# 1-Schematic_Spirulina_controler_board.net
KiCad netlist of a schematic drawn in EasyEDA
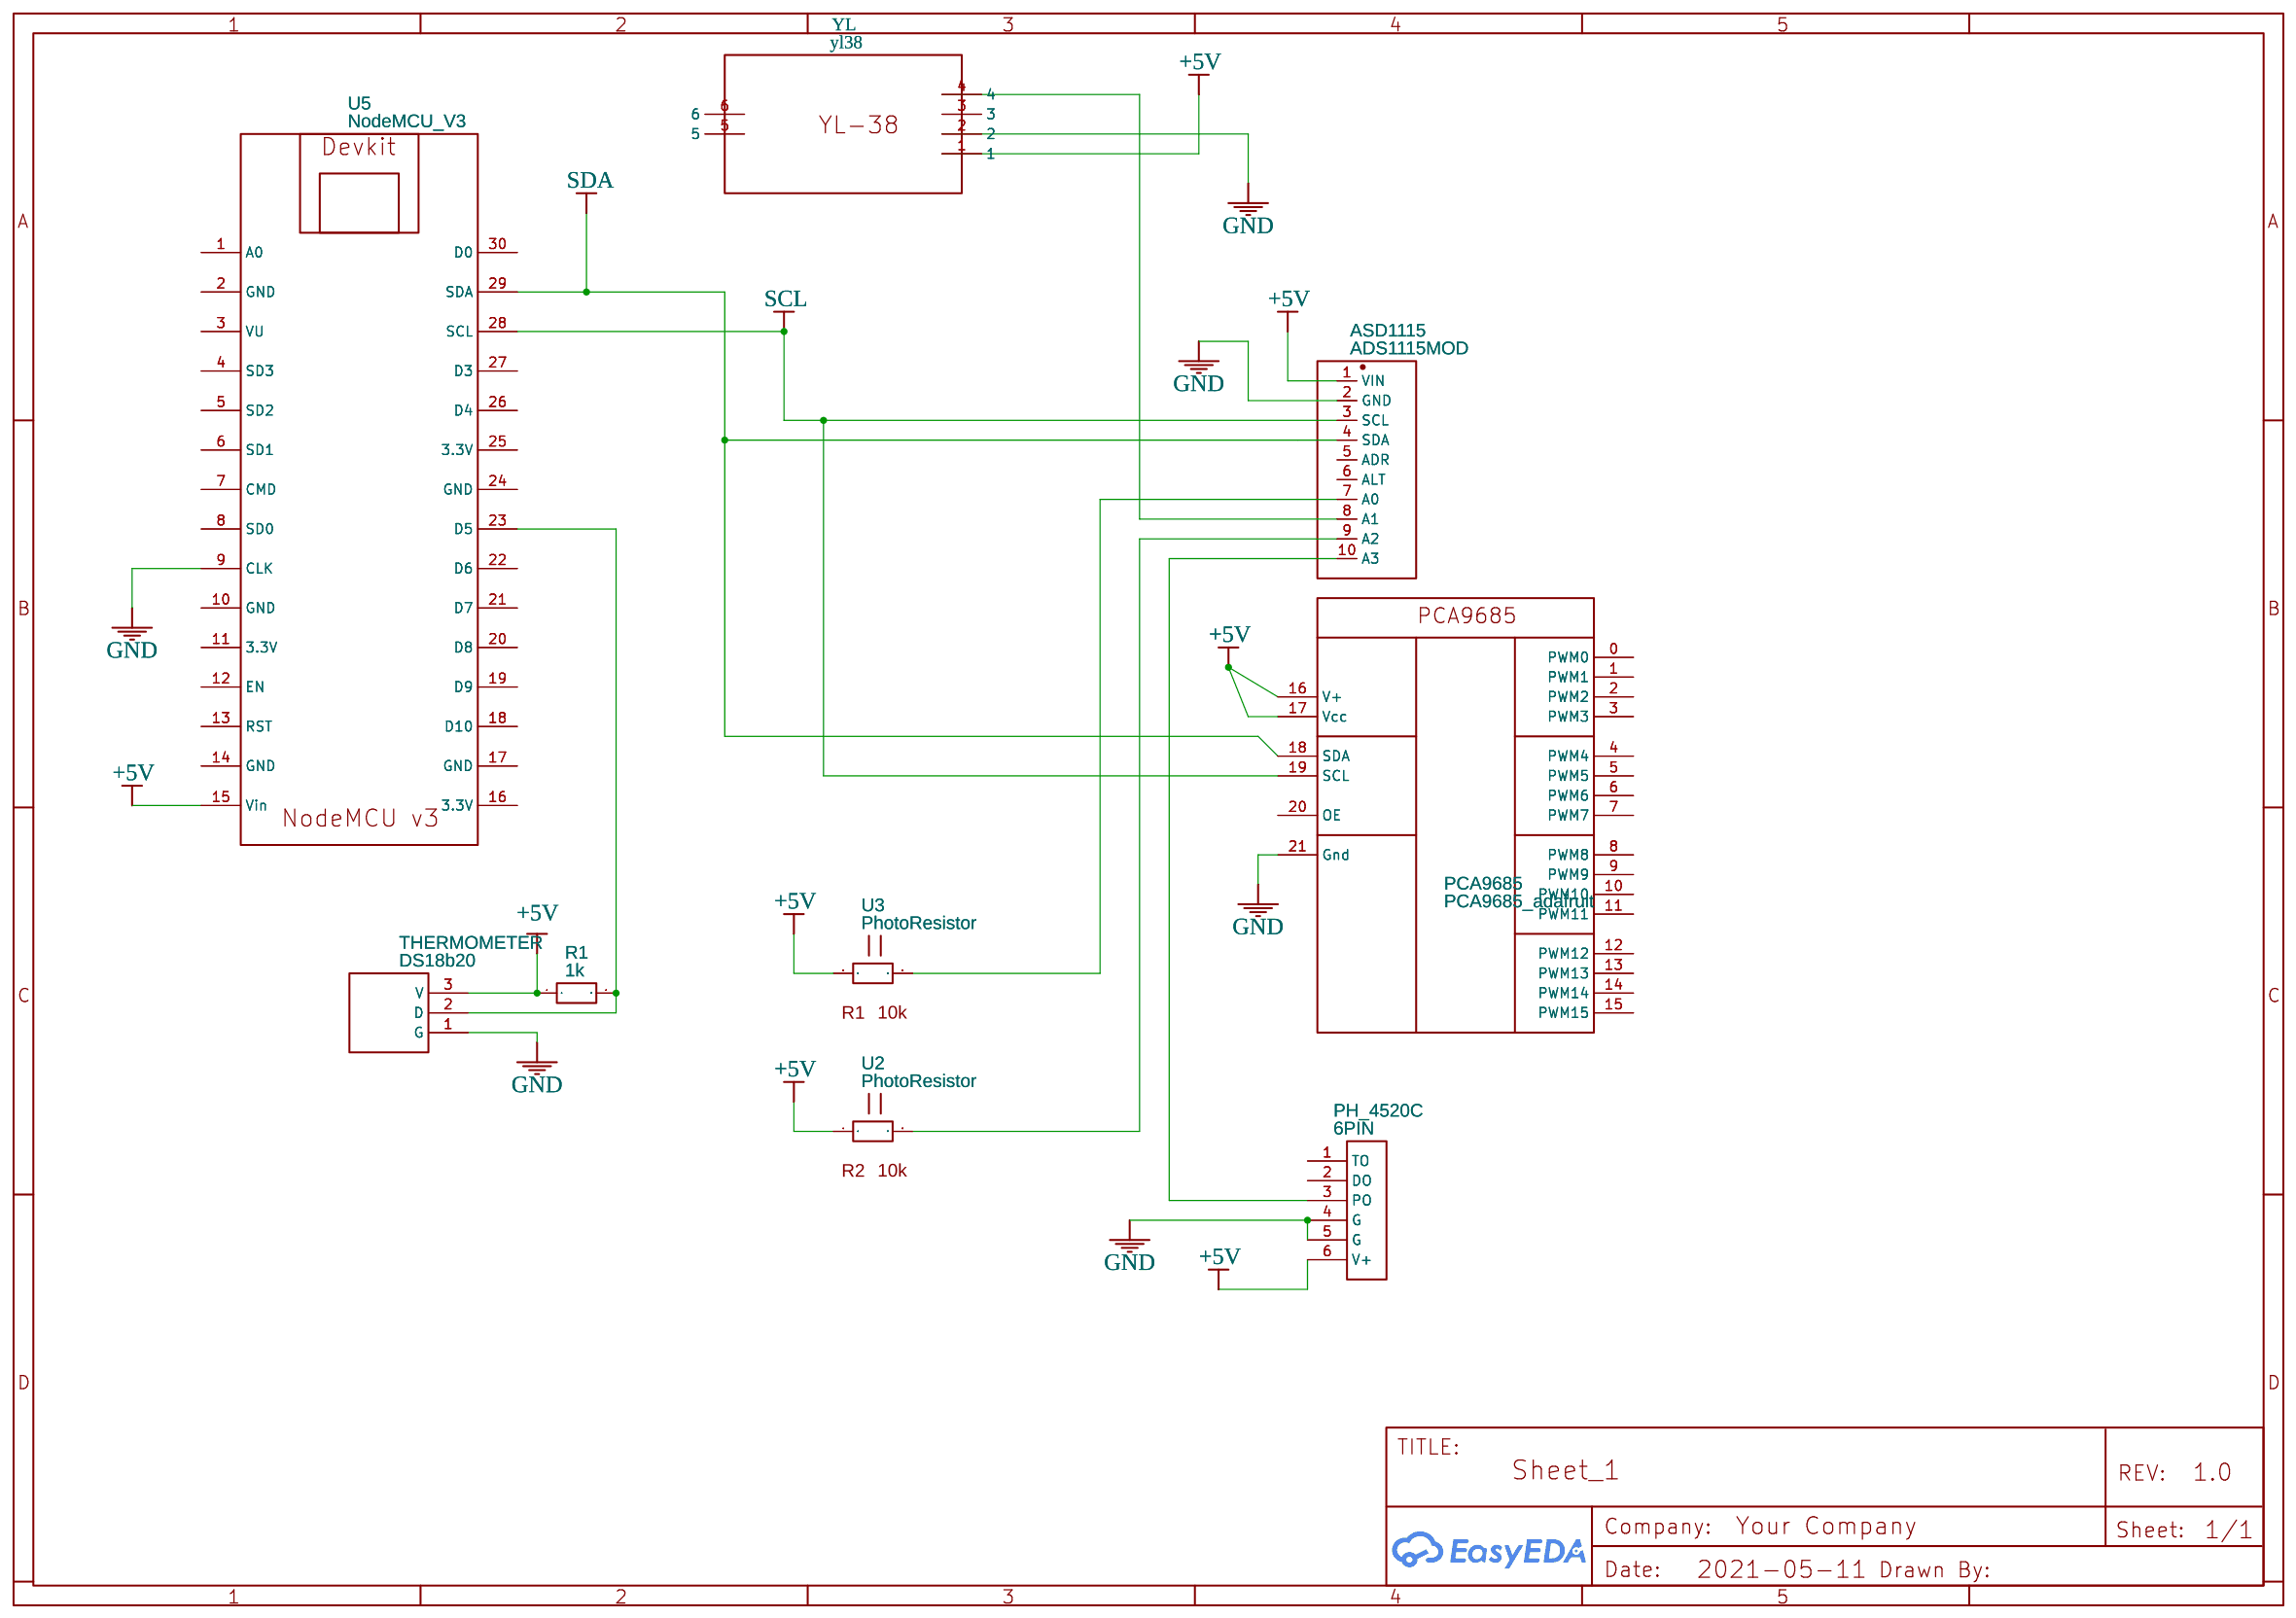
[diagram p0: schematic sheet]

(export (version "E")
  (design (tool "Eeschema 10.0.6"))
  (components
    (comp (ref "ASD1115") (value "ADS1115MOD") (libsource (lib "") (part "ADS1115MOD")))
    (comp (ref "PCA9685") (value "PCA9685_adafruit") (libsource (lib "") (part "PCA9685_adafruit")))
    (comp (ref "PH_4520C") (value "6PIN") (libsource (lib "") (part "6PIN")))
    (comp (ref "R1") (value "1k") (libsource (lib "") (part "R_0201_EU")))
    (comp (ref "THERMOMETER") (value "DS18b20") (libsource (lib "") (part "DS18b20")))
    (comp (ref "U2") (value "PhotoResistor") (libsource (lib "") (part "PhotoResistor_1")))
    (comp (ref "U3") (value "PhotoResistor") (libsource (lib "") (part "PhotoResistor")))
    (comp (ref "U5") (value "NodeMCU_V3") (libsource (lib "") (part "NodeMCU_V3")))
    (comp (ref "YL") (value "yl38") (libsource (lib "") (part "Unknown_420_-755")))
  )
  (nets
    (net (code "1") (name "+5V") (class "Default")
      (node (ref "ASD1115") (pin "1") (pinfunction "VIN_1") (pintype "unspecified"))
      (node (ref "PCA9685") (pin "16") (pinfunction "V+_16") (pintype "unspecified"))
      (node (ref "PCA9685") (pin "17") (pinfunction "Vcc_17") (pintype "unspecified"))
      (node (ref "PH_4520C") (pin "6") (pinfunction "V+_6") (pintype "unspecified"))
      (node (ref "R1") (pin "1") (pinfunction "1_1") (pintype "unspecified"))
      (node (ref "THERMOMETER") (pin "3") (pinfunction "V_3") (pintype "unspecified"))
      (node (ref "U2") (pin "1") (pinfunction "1_1") (pintype "unspecified"))
      (node (ref "U3") (pin "1") (pinfunction "1_1") (pintype "unspecified"))
      (node (ref "U5") (pin "15") (pinfunction "Vin_15") (pintype "unspecified"))
      (node (ref "YL") (pin "1") (pinfunction "1_1") (pintype "unspecified"))
    )
    (net (code "2") (name "GND") (class "Default")
      (node (ref "ASD1115") (pin "2") (pinfunction "GND_2") (pintype "unspecified"))
      (node (ref "PCA9685") (pin "21") (pinfunction "Gnd_21") (pintype "unspecified"))
      (node (ref "PH_4520C") (pin "4") (pinfunction "G_4") (pintype "unspecified"))
      (node (ref "PH_4520C") (pin "5") (pinfunction "G_5") (pintype "unspecified"))
      (node (ref "THERMOMETER") (pin "1") (pinfunction "G_1") (pintype "unspecified"))
      (node (ref "U5") (pin "9") (pinfunction "CLK_9") (pintype "unspecified"))
      (node (ref "YL") (pin "2") (pinfunction "2_2") (pintype "unspecified"))
    )
    (net (code "3") (name "Net-(ASD1115-A0)") (class "Default")
      (node (ref "ASD1115") (pin "7") (pinfunction "A0_7") (pintype "unspecified"))
      (node (ref "U3") (pin "2") (pinfunction "2_2") (pintype "unspecified"))
    )
    (net (code "4") (name "Net-(ASD1115-A1)") (class "Default")
      (node (ref "ASD1115") (pin "8") (pinfunction "A1_8") (pintype "unspecified"))
      (node (ref "YL") (pin "4") (pinfunction "4_4") (pintype "unspecified"))
    )
    (net (code "5") (name "Net-(ASD1115-A2)") (class "Default")
      (node (ref "ASD1115") (pin "9") (pinfunction "A2_9") (pintype "unspecified"))
      (node (ref "U2") (pin "2") (pinfunction "2_2") (pintype "unspecified"))
    )
    (net (code "6") (name "Net-(ASD1115-A3)") (class "Default")
      (node (ref "ASD1115") (pin "10") (pinfunction "A3_10") (pintype "unspecified"))
      (node (ref "PH_4520C") (pin "3") (pinfunction "PO_3") (pintype "unspecified"))
    )
    (net (code "7") (name "Net-(THERMOMETER-D)") (class "Default")
      (node (ref "R1") (pin "2") (pinfunction "2_2") (pintype "unspecified"))
      (node (ref "THERMOMETER") (pin "2") (pinfunction "D_2") (pintype "unspecified"))
      (node (ref "U5") (pin "23") (pinfunction "D5_23") (pintype "unspecified"))
    )
    (net (code "8") (name "SCL") (class "Default")
      (node (ref "ASD1115") (pin "3") (pinfunction "SCL_3") (pintype "unspecified"))
      (node (ref "PCA9685") (pin "19") (pinfunction "SCL_19") (pintype "unspecified"))
      (node (ref "U5") (pin "28") (pinfunction "SCL_28") (pintype "unspecified"))
    )
    (net (code "9") (name "SDA") (class "Default")
      (node (ref "ASD1115") (pin "4") (pinfunction "SDA_4") (pintype "unspecified"))
      (node (ref "PCA9685") (pin "18") (pinfunction "SDA_18") (pintype "unspecified"))
      (node (ref "U5") (pin "29") (pinfunction "SDA_29") (pintype "unspecified"))
    )
    (net (code "10") (name "unconnected-(ASD1115-ADR-Pad5)") (class "Default")
      (node (ref "ASD1115") (pin "5") (pinfunction "ADR_5") (pintype "unspecified"))
    )
    (net (code "11") (name "unconnected-(ASD1115-ALT-Pad6)") (class "Default")
      (node (ref "ASD1115") (pin "6") (pinfunction "ALT_6") (pintype "unspecified"))
    )
    (net (code "12") (name "unconnected-(PCA9685-OE-Pad20)") (class "Default")
      (node (ref "PCA9685") (pin "20") (pinfunction "OE_20") (pintype "unspecified"))
    )
    (net (code "13") (name "unconnected-(PCA9685-PWM0-Pad0)") (class "Default")
      (node (ref "PCA9685") (pin "0") (pinfunction "PWM0_0") (pintype "unspecified"))
    )
    (net (code "14") (name "unconnected-(PCA9685-PWM1-Pad1)") (class "Default")
      (node (ref "PCA9685") (pin "1") (pinfunction "PWM1_1") (pintype "unspecified"))
    )
    (net (code "15") (name "unconnected-(PCA9685-PWM2-Pad2)") (class "Default")
      (node (ref "PCA9685") (pin "2") (pinfunction "PWM2_2") (pintype "unspecified"))
    )
    (net (code "16") (name "unconnected-(PCA9685-PWM3-Pad3)") (class "Default")
      (node (ref "PCA9685") (pin "3") (pinfunction "PWM3_3") (pintype "unspecified"))
    )
    (net (code "17") (name "unconnected-(PCA9685-PWM4-Pad4)") (class "Default")
      (node (ref "PCA9685") (pin "4") (pinfunction "PWM4_4") (pintype "unspecified"))
    )
    (net (code "18") (name "unconnected-(PCA9685-PWM5-Pad5)") (class "Default")
      (node (ref "PCA9685") (pin "5") (pinfunction "PWM5_5") (pintype "unspecified"))
    )
    (net (code "19") (name "unconnected-(PCA9685-PWM6-Pad6)") (class "Default")
      (node (ref "PCA9685") (pin "6") (pinfunction "PWM6_6") (pintype "unspecified"))
    )
    (net (code "20") (name "unconnected-(PCA9685-PWM7-Pad7)") (class "Default")
      (node (ref "PCA9685") (pin "7") (pinfunction "PWM7_7") (pintype "unspecified"))
    )
    (net (code "21") (name "unconnected-(PCA9685-PWM8-Pad8)") (class "Default")
      (node (ref "PCA9685") (pin "8") (pinfunction "PWM8_8") (pintype "unspecified"))
    )
    (net (code "22") (name "unconnected-(PCA9685-PWM9-Pad9)") (class "Default")
      (node (ref "PCA9685") (pin "9") (pinfunction "PWM9_9") (pintype "unspecified"))
    )
    (net (code "23") (name "unconnected-(PCA9685-PWM10-Pad10)") (class "Default")
      (node (ref "PCA9685") (pin "10") (pinfunction "PWM10_10") (pintype "unspecified"))
    )
    (net (code "24") (name "unconnected-(PCA9685-PWM11-Pad11)") (class "Default")
      (node (ref "PCA9685") (pin "11") (pinfunction "PWM11_11") (pintype "unspecified"))
    )
    (net (code "25") (name "unconnected-(PCA9685-PWM12-Pad12)") (class "Default")
      (node (ref "PCA9685") (pin "12") (pinfunction "PWM12_12") (pintype "unspecified"))
    )
    (net (code "26") (name "unconnected-(PCA9685-PWM13-Pad13)") (class "Default")
      (node (ref "PCA9685") (pin "13") (pinfunction "PWM13_13") (pintype "unspecified"))
    )
    (net (code "27") (name "unconnected-(PCA9685-PWM14-Pad14)") (class "Default")
      (node (ref "PCA9685") (pin "14") (pinfunction "PWM14_14") (pintype "unspecified"))
    )
    (net (code "28") (name "unconnected-(PCA9685-PWM15-Pad15)") (class "Default")
      (node (ref "PCA9685") (pin "15") (pinfunction "PWM15_15") (pintype "unspecified"))
    )
    (net (code "29") (name "unconnected-(PH_4520C-DO-Pad2)") (class "Default")
      (node (ref "PH_4520C") (pin "2") (pinfunction "DO_2") (pintype "unspecified"))
    )
    (net (code "30") (name "unconnected-(PH_4520C-TO-Pad1)") (class "Default")
      (node (ref "PH_4520C") (pin "1") (pinfunction "TO_1") (pintype "unspecified"))
    )
    (net (code "31") (name "unconnected-(U5-3.3V-Pad11)") (class "Default")
      (node (ref "U5") (pin "11") (pinfunction "3.3V_11") (pintype "unspecified"))
    )
    (net (code "32") (name "unconnected-(U5-3.3V-Pad16)") (class "Default")
      (node (ref "U5") (pin "16") (pinfunction "3.3V_16") (pintype "unspecified"))
    )
    (net (code "33") (name "unconnected-(U5-3.3V-Pad25)") (class "Default")
      (node (ref "U5") (pin "25") (pinfunction "3.3V_25") (pintype "unspecified"))
    )
    (net (code "34") (name "unconnected-(U5-A0-Pad1)") (class "Default")
      (node (ref "U5") (pin "1") (pinfunction "A0_1") (pintype "unspecified"))
    )
    (net (code "35") (name "unconnected-(U5-CMD-Pad7)") (class "Default")
      (node (ref "U5") (pin "7") (pinfunction "CMD_7") (pintype "unspecified"))
    )
    (net (code "36") (name "unconnected-(U5-D0-Pad30)") (class "Default")
      (node (ref "U5") (pin "30") (pinfunction "D0_30") (pintype "unspecified"))
    )
    (net (code "37") (name "unconnected-(U5-D3-Pad27)") (class "Default")
      (node (ref "U5") (pin "27") (pinfunction "D3_27") (pintype "unspecified"))
    )
    (net (code "38") (name "unconnected-(U5-D4-Pad26)") (class "Default")
      (node (ref "U5") (pin "26") (pinfunction "D4_26") (pintype "unspecified"))
    )
    (net (code "39") (name "unconnected-(U5-D6-Pad22)") (class "Default")
      (node (ref "U5") (pin "22") (pinfunction "D6_22") (pintype "unspecified"))
    )
    (net (code "40") (name "unconnected-(U5-D7-Pad21)") (class "Default")
      (node (ref "U5") (pin "21") (pinfunction "D7_21") (pintype "unspecified"))
    )
    (net (code "41") (name "unconnected-(U5-D8-Pad20)") (class "Default")
      (node (ref "U5") (pin "20") (pinfunction "D8_20") (pintype "unspecified"))
    )
    (net (code "42") (name "unconnected-(U5-D9-Pad19)") (class "Default")
      (node (ref "U5") (pin "19") (pinfunction "D9_19") (pintype "unspecified"))
    )
    (net (code "43") (name "unconnected-(U5-D10-Pad18)") (class "Default")
      (node (ref "U5") (pin "18") (pinfunction "D10_18") (pintype "unspecified"))
    )
    (net (code "44") (name "unconnected-(U5-EN-Pad12)") (class "Default")
      (node (ref "U5") (pin "12") (pinfunction "EN_12") (pintype "unspecified"))
    )
    (net (code "45") (name "unconnected-(U5-GND-Pad2)") (class "Default")
      (node (ref "U5") (pin "2") (pinfunction "GND_2") (pintype "unspecified"))
    )
    (net (code "46") (name "unconnected-(U5-GND-Pad10)") (class "Default")
      (node (ref "U5") (pin "10") (pinfunction "GND_10") (pintype "unspecified"))
    )
    (net (code "47") (name "unconnected-(U5-GND-Pad14)") (class "Default")
      (node (ref "U5") (pin "14") (pinfunction "GND_14") (pintype "unspecified"))
    )
    (net (code "48") (name "unconnected-(U5-GND-Pad17)") (class "Default")
      (node (ref "U5") (pin "17") (pinfunction "GND_17") (pintype "unspecified"))
    )
    (net (code "49") (name "unconnected-(U5-GND-Pad24)") (class "Default")
      (node (ref "U5") (pin "24") (pinfunction "GND_24") (pintype "unspecified"))
    )
    (net (code "50") (name "unconnected-(U5-RST-Pad13)") (class "Default")
      (node (ref "U5") (pin "13") (pinfunction "RST_13") (pintype "unspecified"))
    )
    (net (code "51") (name "unconnected-(U5-SD0-Pad8)") (class "Default")
      (node (ref "U5") (pin "8") (pinfunction "SD0_8") (pintype "unspecified"))
    )
    (net (code "52") (name "unconnected-(U5-SD1-Pad6)") (class "Default")
      (node (ref "U5") (pin "6") (pinfunction "SD1_6") (pintype "unspecified"))
    )
    (net (code "53") (name "unconnected-(U5-SD2-Pad5)") (class "Default")
      (node (ref "U5") (pin "5") (pinfunction "SD2_5") (pintype "unspecified"))
    )
    (net (code "54") (name "unconnected-(U5-SD3-Pad4)") (class "Default")
      (node (ref "U5") (pin "4") (pinfunction "SD3_4") (pintype "unspecified"))
    )
    (net (code "55") (name "unconnected-(U5-VU-Pad3)") (class "Default")
      (node (ref "U5") (pin "3") (pinfunction "VU_3") (pintype "unspecified"))
    )
    (net (code "56") (name "unconnected-(YL-Pad3)") (class "Default")
      (node (ref "YL") (pin "3") (pinfunction "3_3") (pintype "unspecified"))
    )
    (net (code "57") (name "unconnected-(YL-Pad5)") (class "Default")
      (node (ref "YL") (pin "5") (pinfunction "5_5") (pintype "unspecified"))
    )
    (net (code "58") (name "unconnected-(YL-Pad6)") (class "Default")
      (node (ref "YL") (pin "6") (pinfunction "6_6") (pintype "unspecified"))
    )
  )
)
